# Inverter.net
KiCad netlist of a schematic drawn in Altium Designer
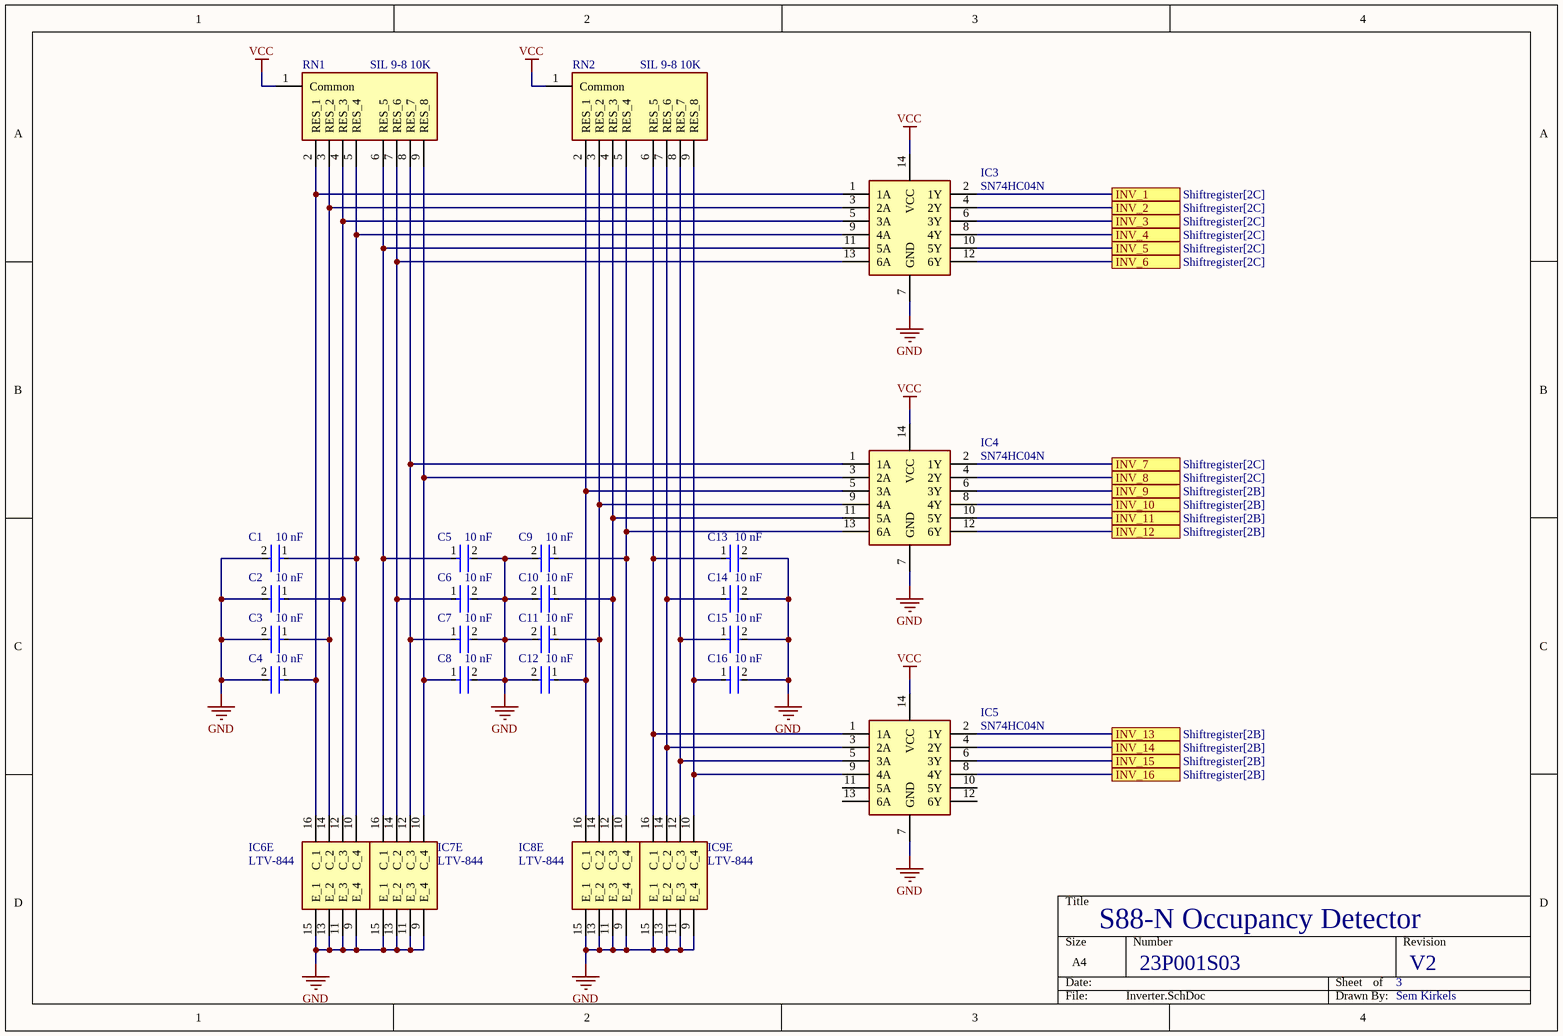
[diagram p0: Inverter.SchDoc]

(export (version "E")
  (design (tool "Eeschema 10.0.6"))
  (components
    (comp (ref "C1")
      (value "10 nF")
      (footprint "Capacitor")
      (fields (field (name "TOLERANCE") "20%") (field (name "VOLTAGE") "500V"))
      (libsource (lib "Schematic_Library_S88N") (part "Capacitor"))
    )
    (comp (ref "C2")
      (value "10 nF")
      (footprint "Capacitor")
      (fields (field (name "TOLERANCE") "20%") (field (name "VOLTAGE") "500V"))
      (libsource (lib "Schematic_Library_S88N") (part "Capacitor"))
    )
    (comp (ref "C3")
      (value "10 nF")
      (footprint "Capacitor")
      (fields (field (name "TOLERANCE") "20%") (field (name "VOLTAGE") "500V"))
      (libsource (lib "Schematic_Library_S88N") (part "Capacitor"))
    )
    (comp (ref "C4")
      (value "10 nF")
      (footprint "Capacitor")
      (fields (field (name "TOLERANCE") "20%") (field (name "VOLTAGE") "500V"))
      (libsource (lib "Schematic_Library_S88N") (part "Capacitor"))
    )
    (comp (ref "C5")
      (value "10 nF")
      (footprint "Capacitor")
      (fields (field (name "TOLERANCE") "20%") (field (name "VOLTAGE") "500V"))
      (libsource (lib "Schematic_Library_S88N") (part "Capacitor"))
    )
    (comp (ref "C6")
      (value "10 nF")
      (footprint "Capacitor")
      (fields (field (name "TOLERANCE") "20%") (field (name "VOLTAGE") "500V"))
      (libsource (lib "Schematic_Library_S88N") (part "Capacitor"))
    )
    (comp (ref "C7")
      (value "10 nF")
      (footprint "Capacitor")
      (fields (field (name "TOLERANCE") "20%") (field (name "VOLTAGE") "500V"))
      (libsource (lib "Schematic_Library_S88N") (part "Capacitor"))
    )
    (comp (ref "C8")
      (value "10 nF")
      (footprint "Capacitor")
      (fields (field (name "TOLERANCE") "20%") (field (name "VOLTAGE") "500V"))
      (libsource (lib "Schematic_Library_S88N") (part "Capacitor"))
    )
    (comp (ref "C9")
      (value "10 nF")
      (footprint "Capacitor")
      (fields (field (name "TOLERANCE") "20%") (field (name "VOLTAGE") "500V"))
      (libsource (lib "Schematic_Library_S88N") (part "Capacitor"))
    )
    (comp (ref "C10")
      (value "10 nF")
      (footprint "Capacitor")
      (fields (field (name "TOLERANCE") "20%") (field (name "VOLTAGE") "500V"))
      (libsource (lib "Schematic_Library_S88N") (part "Capacitor"))
    )
    (comp (ref "C11")
      (value "10 nF")
      (footprint "Capacitor")
      (fields (field (name "TOLERANCE") "20%") (field (name "VOLTAGE") "500V"))
      (libsource (lib "Schematic_Library_S88N") (part "Capacitor"))
    )
    (comp (ref "C12")
      (value "10 nF")
      (footprint "Capacitor")
      (fields (field (name "TOLERANCE") "20%") (field (name "VOLTAGE") "500V"))
      (libsource (lib "Schematic_Library_S88N") (part "Capacitor"))
    )
    (comp (ref "C13")
      (value "10 nF")
      (footprint "Capacitor")
      (fields (field (name "TOLERANCE") "20%") (field (name "VOLTAGE") "500V"))
      (libsource (lib "Schematic_Library_S88N") (part "Capacitor"))
    )
    (comp (ref "C14")
      (value "10 nF")
      (footprint "Capacitor")
      (fields (field (name "TOLERANCE") "20%") (field (name "VOLTAGE") "500V"))
      (libsource (lib "Schematic_Library_S88N") (part "Capacitor"))
    )
    (comp (ref "C15")
      (value "10 nF")
      (footprint "Capacitor")
      (fields (field (name "TOLERANCE") "20%") (field (name "VOLTAGE") "500V"))
      (libsource (lib "Schematic_Library_S88N") (part "Capacitor"))
    )
    (comp (ref "C16")
      (value "10 nF")
      (footprint "Capacitor")
      (fields (field (name "TOLERANCE") "20%") (field (name "VOLTAGE") "500V"))
      (libsource (lib "Schematic_Library_S88N") (part "Capacitor"))
    )
    (comp (ref "IC3")
      (value "SN74HC04N")
      (footprint "SN74HC04")
      (description "Integrated Circuit")
      (fields (field (name "MOUSER PART NUMBER") "595-SN74HC04N"))
      (libsource (lib "Schematic_Library_S88N") (part "SN74HC04N"))
    )
    (comp (ref "IC4")
      (value "SN74HC04N")
      (footprint "SN74HC04")
      (description "Integrated Circuit")
      (fields (field (name "MOUSER PART NUMBER") "595-SN74HC04N"))
      (libsource (lib "Schematic_Library_S88N") (part "SN74HC04N"))
    )
    (comp (ref "IC5")
      (value "SN74HC04N")
      (footprint "SN74HC04")
      (description "Integrated Circuit")
      (fields (field (name "MOUSER PART NUMBER") "595-SN74HC04N"))
      (libsource (lib "Schematic_Library_S88N") (part "SN74HC04N"))
    )
    (comp (ref "IC6")
      (value "LTV-844")
      (footprint "CD4014")
      (description "Integrated Circuit")
      (fields (field (name "MOUSER PART NUMBER") "859-LTV-844"))
      (libsource (lib "Schematic_Library_S88N") (part "LTV-844"))
    )
    (comp (ref "IC7")
      (value "LTV-844")
      (footprint "CD4014")
      (description "Integrated Circuit")
      (fields (field (name "MOUSER PART NUMBER") "859-LTV-844"))
      (libsource (lib "Schematic_Library_S88N") (part "LTV-844"))
    )
    (comp (ref "IC8")
      (value "LTV-844")
      (footprint "CD4014")
      (description "Integrated Circuit")
      (fields (field (name "MOUSER PART NUMBER") "859-LTV-844"))
      (libsource (lib "Schematic_Library_S88N") (part "LTV-844"))
    )
    (comp (ref "IC9")
      (value "LTV-844")
      (footprint "CD4014")
      (description "Integrated Circuit")
      (fields (field (name "MOUSER PART NUMBER") "859-LTV-844"))
      (libsource (lib "Schematic_Library_S88N") (part "LTV-844"))
    )
    (comp (ref "RN1")
      (value "SIL 9-8 10K")
      (footprint "SIL 9-8 10K")
      (description "CSC09A0110K0GEK")
      (fields (field (name "MOUSER PART NUMBER") "71-CSC09A0110K0GEK"))
      (libsource (lib "Schematic_Library_S88N") (part "SIL 9-8 10K"))
    )
    (comp (ref "RN2")
      (value "SIL 9-8 10K")
      (footprint "SIL 9-8 10K")
      (description "CSC09A0110K0GEK")
      (fields (field (name "MOUSER PART NUMBER") "71-CSC09A0110K0GEK"))
      (libsource (lib "Schematic_Library_S88N") (part "SIL 9-8 10K"))
    )
  )
  (nets
    (net (code "1") (name "/INV_1") (class "Default")
      (node (ref "IC3") (pin "2") (pinfunction "1Y_2") (pintype "passive"))
    )
    (net (code "2") (name "/INV_2") (class "Default")
      (node (ref "IC3") (pin "4") (pinfunction "2Y_4") (pintype "passive"))
    )
    (net (code "3") (name "/INV_3") (class "Default")
      (node (ref "IC3") (pin "6") (pinfunction "3Y_6") (pintype "passive"))
    )
    (net (code "4") (name "/INV_4") (class "Default")
      (node (ref "IC3") (pin "8") (pinfunction "4Y_8") (pintype "passive"))
    )
    (net (code "5") (name "/INV_5") (class "Default")
      (node (ref "IC3") (pin "10") (pinfunction "5Y_10") (pintype "passive"))
    )
    (net (code "6") (name "/INV_6") (class "Default")
      (node (ref "IC3") (pin "12") (pinfunction "6Y_12") (pintype "passive"))
    )
    (net (code "7") (name "/INV_7") (class "Default")
      (node (ref "IC4") (pin "2") (pinfunction "1Y_2") (pintype "passive"))
    )
    (net (code "8") (name "/INV_8") (class "Default")
      (node (ref "IC4") (pin "4") (pinfunction "2Y_4") (pintype "passive"))
    )
    (net (code "9") (name "/INV_9") (class "Default")
      (node (ref "IC4") (pin "6") (pinfunction "3Y_6") (pintype "passive"))
    )
    (net (code "10") (name "/INV_10") (class "Default")
      (node (ref "IC4") (pin "8") (pinfunction "4Y_8") (pintype "passive"))
    )
    (net (code "11") (name "/INV_11") (class "Default")
      (node (ref "IC4") (pin "10") (pinfunction "5Y_10") (pintype "passive"))
    )
    (net (code "12") (name "/INV_12") (class "Default")
      (node (ref "IC4") (pin "12") (pinfunction "6Y_12") (pintype "passive"))
    )
    (net (code "13") (name "/INV_13") (class "Default")
      (node (ref "IC5") (pin "2") (pinfunction "1Y_2") (pintype "passive"))
    )
    (net (code "14") (name "/INV_14") (class "Default")
      (node (ref "IC5") (pin "4") (pinfunction "2Y_4") (pintype "passive"))
    )
    (net (code "15") (name "/INV_15") (class "Default")
      (node (ref "IC5") (pin "6") (pinfunction "3Y_6") (pintype "passive"))
    )
    (net (code "16") (name "/INV_16") (class "Default")
      (node (ref "IC5") (pin "8") (pinfunction "4Y_8") (pintype "passive"))
    )
    (net (code "17") (name "GND") (class "Default")
      (node (ref "C1") (pin "2") (pinfunction "2_2") (pintype "passive"))
      (node (ref "C10") (pin "2") (pinfunction "2_2") (pintype "passive"))
      (node (ref "C11") (pin "2") (pinfunction "2_2") (pintype "passive"))
      (node (ref "C12") (pin "2") (pinfunction "2_2") (pintype "passive"))
      (node (ref "C13") (pin "2") (pinfunction "2_2") (pintype "passive"))
      (node (ref "C14") (pin "2") (pinfunction "2_2") (pintype "passive"))
      (node (ref "C15") (pin "2") (pinfunction "2_2") (pintype "passive"))
      (node (ref "C16") (pin "2") (pinfunction "2_2") (pintype "passive"))
      (node (ref "C2") (pin "2") (pinfunction "2_2") (pintype "passive"))
      (node (ref "C3") (pin "2") (pinfunction "2_2") (pintype "passive"))
      (node (ref "C4") (pin "2") (pinfunction "2_2") (pintype "passive"))
      (node (ref "C5") (pin "2") (pinfunction "2_2") (pintype "passive"))
      (node (ref "C6") (pin "2") (pinfunction "2_2") (pintype "passive"))
      (node (ref "C7") (pin "2") (pinfunction "2_2") (pintype "passive"))
      (node (ref "C8") (pin "2") (pinfunction "2_2") (pintype "passive"))
      (node (ref "C9") (pin "2") (pinfunction "2_2") (pintype "passive"))
      (node (ref "IC3") (pin "7") (pinfunction "GND_7") (pintype "passive"))
      (node (ref "IC4") (pin "7") (pinfunction "GND_7") (pintype "passive"))
      (node (ref "IC5") (pin "7") (pinfunction "GND_7") (pintype "passive"))
      (node (ref "IC6") (pin "11") (pinfunction "E_3_11") (pintype "passive"))
      (node (ref "IC6") (pin "13") (pinfunction "E_2_13") (pintype "passive"))
      (node (ref "IC6") (pin "15") (pinfunction "E_1_15") (pintype "passive"))
      (node (ref "IC6") (pin "9") (pinfunction "E_4_9") (pintype "passive"))
      (node (ref "IC7") (pin "11") (pinfunction "E_3_11") (pintype "passive"))
      (node (ref "IC7") (pin "13") (pinfunction "E_2_13") (pintype "passive"))
      (node (ref "IC7") (pin "15") (pinfunction "E_1_15") (pintype "passive"))
      (node (ref "IC7") (pin "9") (pinfunction "E_4_9") (pintype "passive"))
      (node (ref "IC8") (pin "11") (pinfunction "E_3_11") (pintype "passive"))
      (node (ref "IC8") (pin "13") (pinfunction "E_2_13") (pintype "passive"))
      (node (ref "IC8") (pin "15") (pinfunction "E_1_15") (pintype "passive"))
      (node (ref "IC8") (pin "9") (pinfunction "E_4_9") (pintype "passive"))
      (node (ref "IC9") (pin "11") (pinfunction "E_3_11") (pintype "passive"))
      (node (ref "IC9") (pin "13") (pinfunction "E_2_13") (pintype "passive"))
      (node (ref "IC9") (pin "15") (pinfunction "E_1_15") (pintype "passive"))
      (node (ref "IC9") (pin "9") (pinfunction "E_4_9") (pintype "passive"))
    )
    (net (code "18") (name "Net-(IC3-1A)") (class "Default")
      (node (ref "C4") (pin "1") (pinfunction "1_1") (pintype "passive"))
      (node (ref "IC3") (pin "1") (pinfunction "1A_1") (pintype "passive"))
      (node (ref "IC6") (pin "16") (pinfunction "C_1_16") (pintype "passive"))
      (node (ref "RN1") (pin "2") (pinfunction "RES_1_2") (pintype "passive"))
    )
    (net (code "19") (name "Net-(IC3-2A)") (class "Default")
      (node (ref "C3") (pin "1") (pinfunction "1_1") (pintype "passive"))
      (node (ref "IC3") (pin "3") (pinfunction "2A_3") (pintype "passive"))
      (node (ref "IC6") (pin "14") (pinfunction "C_2_14") (pintype "passive"))
      (node (ref "RN1") (pin "3") (pinfunction "RES_2_3") (pintype "passive"))
    )
    (net (code "20") (name "Net-(IC3-3A)") (class "Default")
      (node (ref "C2") (pin "1") (pinfunction "1_1") (pintype "passive"))
      (node (ref "IC3") (pin "5") (pinfunction "3A_5") (pintype "passive"))
      (node (ref "IC6") (pin "12") (pinfunction "C_3_12") (pintype "passive"))
      (node (ref "RN1") (pin "4") (pinfunction "RES_3_4") (pintype "passive"))
    )
    (net (code "21") (name "Net-(IC3-4A)") (class "Default")
      (node (ref "C1") (pin "1") (pinfunction "1_1") (pintype "passive"))
      (node (ref "IC3") (pin "9") (pinfunction "4A_9") (pintype "passive"))
      (node (ref "IC6") (pin "10") (pinfunction "C_4_10") (pintype "passive"))
      (node (ref "RN1") (pin "5") (pinfunction "RES_4_5") (pintype "passive"))
    )
    (net (code "22") (name "Net-(IC3-5A)") (class "Default")
      (node (ref "C5") (pin "1") (pinfunction "1_1") (pintype "passive"))
      (node (ref "IC3") (pin "11") (pinfunction "5A_11") (pintype "passive"))
      (node (ref "IC7") (pin "16") (pinfunction "C_1_16") (pintype "passive"))
      (node (ref "RN1") (pin "6") (pinfunction "RES_5_6") (pintype "passive"))
    )
    (net (code "23") (name "Net-(IC3-6A)") (class "Default")
      (node (ref "C6") (pin "1") (pinfunction "1_1") (pintype "passive"))
      (node (ref "IC3") (pin "13") (pinfunction "6A_13") (pintype "passive"))
      (node (ref "IC7") (pin "14") (pinfunction "C_2_14") (pintype "passive"))
      (node (ref "RN1") (pin "7") (pinfunction "RES_6_7") (pintype "passive"))
    )
    (net (code "24") (name "Net-(IC4-1A)") (class "Default")
      (node (ref "C7") (pin "1") (pinfunction "1_1") (pintype "passive"))
      (node (ref "IC4") (pin "1") (pinfunction "1A_1") (pintype "passive"))
      (node (ref "IC7") (pin "12") (pinfunction "C_3_12") (pintype "passive"))
      (node (ref "RN1") (pin "8") (pinfunction "RES_7_8") (pintype "passive"))
    )
    (net (code "25") (name "Net-(IC4-2A)") (class "Default")
      (node (ref "C8") (pin "1") (pinfunction "1_1") (pintype "passive"))
      (node (ref "IC4") (pin "3") (pinfunction "2A_3") (pintype "passive"))
      (node (ref "IC7") (pin "10") (pinfunction "C_4_10") (pintype "passive"))
      (node (ref "RN1") (pin "9") (pinfunction "RES_8_9") (pintype "passive"))
    )
    (net (code "26") (name "Net-(IC4-3A)") (class "Default")
      (node (ref "C12") (pin "1") (pinfunction "1_1") (pintype "passive"))
      (node (ref "IC4") (pin "5") (pinfunction "3A_5") (pintype "passive"))
      (node (ref "IC8") (pin "16") (pinfunction "C_1_16") (pintype "passive"))
      (node (ref "RN2") (pin "2") (pinfunction "RES_1_2") (pintype "passive"))
    )
    (net (code "27") (name "Net-(IC4-4A)") (class "Default")
      (node (ref "C11") (pin "1") (pinfunction "1_1") (pintype "passive"))
      (node (ref "IC4") (pin "9") (pinfunction "4A_9") (pintype "passive"))
      (node (ref "IC8") (pin "14") (pinfunction "C_2_14") (pintype "passive"))
      (node (ref "RN2") (pin "3") (pinfunction "RES_2_3") (pintype "passive"))
    )
    (net (code "28") (name "Net-(IC4-5A)") (class "Default")
      (node (ref "C10") (pin "1") (pinfunction "1_1") (pintype "passive"))
      (node (ref "IC4") (pin "11") (pinfunction "5A_11") (pintype "passive"))
      (node (ref "IC8") (pin "12") (pinfunction "C_3_12") (pintype "passive"))
      (node (ref "RN2") (pin "4") (pinfunction "RES_3_4") (pintype "passive"))
    )
    (net (code "29") (name "Net-(IC4-6A)") (class "Default")
      (node (ref "C9") (pin "1") (pinfunction "1_1") (pintype "passive"))
      (node (ref "IC4") (pin "13") (pinfunction "6A_13") (pintype "passive"))
      (node (ref "IC8") (pin "10") (pinfunction "C_4_10") (pintype "passive"))
      (node (ref "RN2") (pin "5") (pinfunction "RES_4_5") (pintype "passive"))
    )
    (net (code "30") (name "Net-(IC5-1A)") (class "Default")
      (node (ref "C13") (pin "1") (pinfunction "1_1") (pintype "passive"))
      (node (ref "IC5") (pin "1") (pinfunction "1A_1") (pintype "passive"))
      (node (ref "IC9") (pin "16") (pinfunction "C_1_16") (pintype "passive"))
      (node (ref "RN2") (pin "6") (pinfunction "RES_5_6") (pintype "passive"))
    )
    (net (code "31") (name "Net-(IC5-2A)") (class "Default")
      (node (ref "C14") (pin "1") (pinfunction "1_1") (pintype "passive"))
      (node (ref "IC5") (pin "3") (pinfunction "2A_3") (pintype "passive"))
      (node (ref "IC9") (pin "14") (pinfunction "C_2_14") (pintype "passive"))
      (node (ref "RN2") (pin "7") (pinfunction "RES_6_7") (pintype "passive"))
    )
    (net (code "32") (name "Net-(IC5-3A)") (class "Default")
      (node (ref "C15") (pin "1") (pinfunction "1_1") (pintype "passive"))
      (node (ref "IC5") (pin "5") (pinfunction "3A_5") (pintype "passive"))
      (node (ref "IC9") (pin "12") (pinfunction "C_3_12") (pintype "passive"))
      (node (ref "RN2") (pin "8") (pinfunction "RES_7_8") (pintype "passive"))
    )
    (net (code "33") (name "Net-(IC5-4A)") (class "Default")
      (node (ref "C16") (pin "1") (pinfunction "1_1") (pintype "passive"))
      (node (ref "IC5") (pin "9") (pinfunction "4A_9") (pintype "passive"))
      (node (ref "IC9") (pin "10") (pinfunction "C_4_10") (pintype "passive"))
      (node (ref "RN2") (pin "9") (pinfunction "RES_8_9") (pintype "passive"))
    )
    (net (code "34") (name "VCC") (class "Default")
      (node (ref "IC3") (pin "14") (pinfunction "VCC_14") (pintype "passive"))
      (node (ref "IC4") (pin "14") (pinfunction "VCC_14") (pintype "passive"))
      (node (ref "IC5") (pin "14") (pinfunction "VCC_14") (pintype "passive"))
      (node (ref "RN1") (pin "1") (pinfunction "Common_1") (pintype "passive"))
      (node (ref "RN2") (pin "1") (pinfunction "Common_1") (pintype "passive"))
    )
    (net (code "35") (name "unconnected-(IC5-5A-Pad11)") (class "Default")
      (node (ref "IC5") (pin "11") (pinfunction "5A_11") (pintype "passive"))
    )
    (net (code "36") (name "unconnected-(IC5-5Y-Pad10)") (class "Default")
      (node (ref "IC5") (pin "10") (pinfunction "5Y_10") (pintype "passive"))
    )
    (net (code "37") (name "unconnected-(IC5-6A-Pad13)") (class "Default")
      (node (ref "IC5") (pin "13") (pinfunction "6A_13") (pintype "passive"))
    )
    (net (code "38") (name "unconnected-(IC5-6Y-Pad12)") (class "Default")
      (node (ref "IC5") (pin "12") (pinfunction "6Y_12") (pintype "passive"))
    )
  )
)
